# Schematic_Top_Rev4.net
KiCad netlist of a schematic drawn in Altium Designer
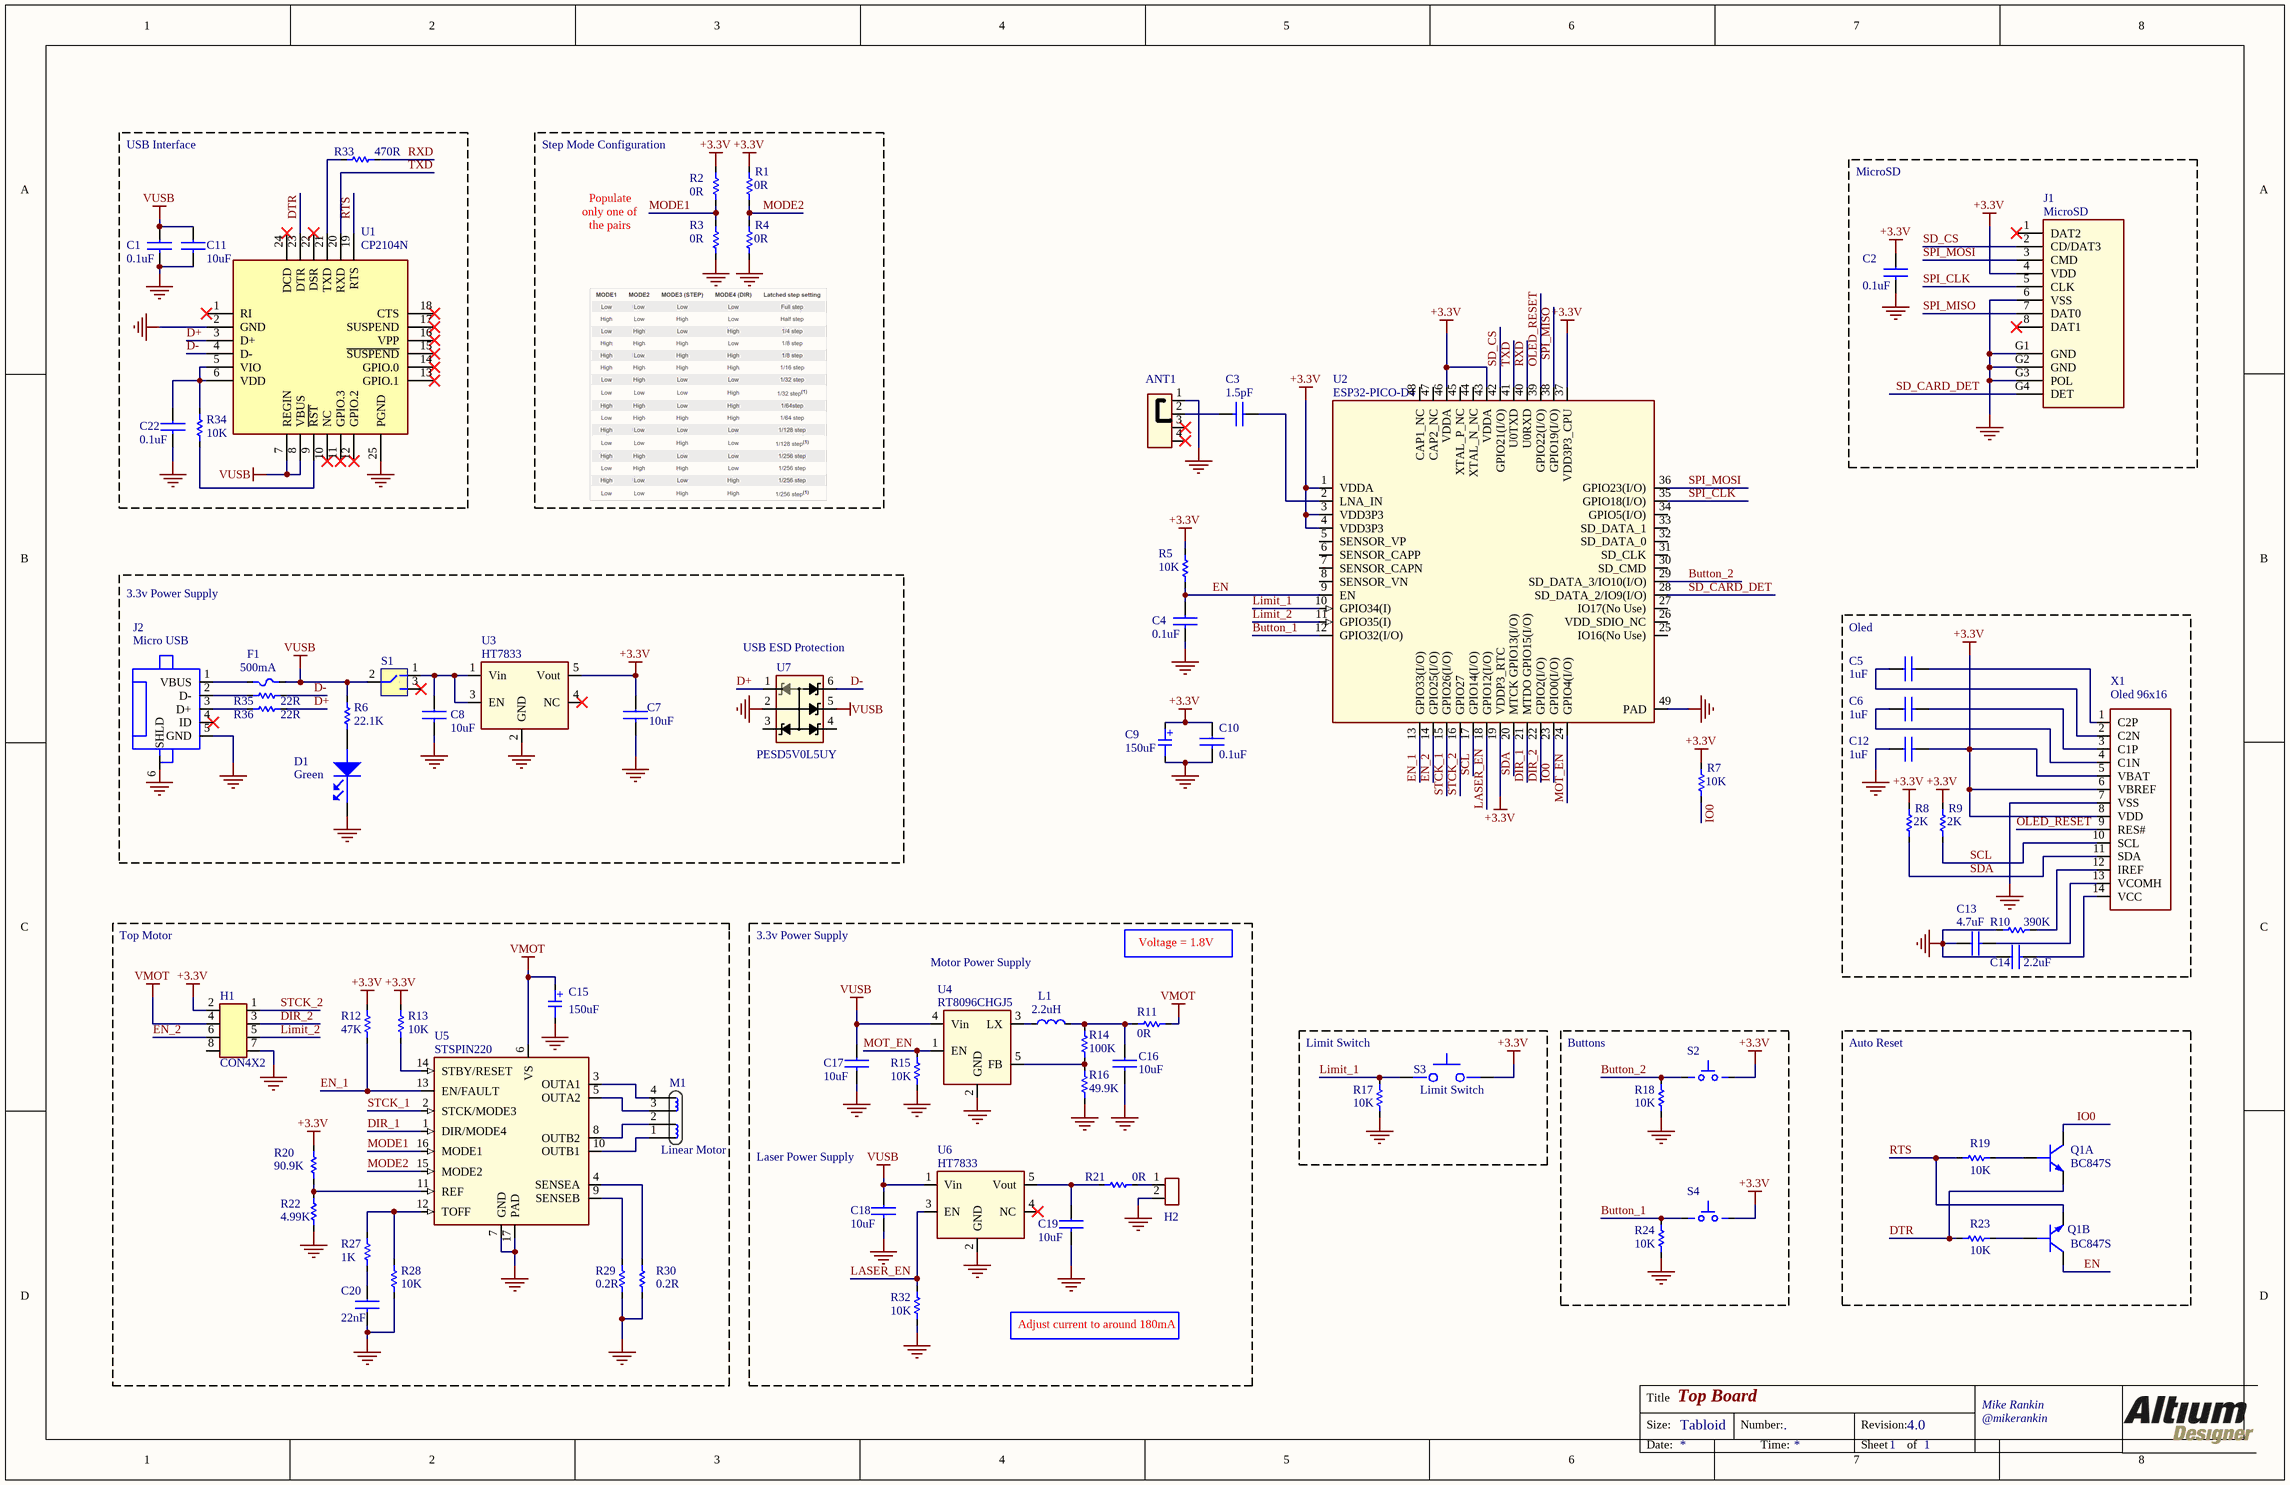
[diagram p0: Schematic_Top_Rev4.SchDoc]

(export (version "E")
  (design (tool "Eeschema 10.0.6"))
  (components
    (comp (ref "ANT1")
      (value "RF ANT 2.4GHZ STAMPED MET SLD")
      (footprint "PRO-OB-440")
      (fields (field (name "MANUFACTURER") "Proant AB") (field (name "PART_NUMBER") "PRO-OB-440"))
      (libsource (lib "MAR") (part "PRO-OB-440"))
    )
    (comp (ref "C1")
      (value "0.1uF")
      (footprint "CAPC1005X56N")
      (description "CAP 0.1uF 16V 0402")
      (fields (field (name "PART_NUMBER") "C60474") (field (name "MANUFACTURER") "Yageo"))
      (libsource (lib "MAR") (part "CAP_0402"))
    )
    (comp (ref "C2")
      (value "0.1uF")
      (footprint "CAPC1005X56N")
      (description "CAP 0.1uF 16V 0402")
      (fields (field (name "PART_NUMBER") "C60474") (field (name "MANUFACTURER") "Yageo"))
      (libsource (lib "MAR") (part "CAP_0402"))
    )
    (comp (ref "C3")
      (value "1.5pF")
      (footprint "CAPC1005X56N")
      (description "CAP 1.5pF 0402")
      (fields (field (name "PART_NUMBER") "C147344") (field (name "MANUFACTURER") "Dafron"))
      (libsource (lib "MAR") (part "CAP_0402"))
    )
    (comp (ref "C4")
      (value "0.1uF")
      (footprint "CAPC1005X56N")
      (description "CAP 0.1uF 16V 0402")
      (fields (field (name "PART_NUMBER") "C60474") (field (name "MANUFACTURER") "Yageo"))
      (libsource (lib "MAR") (part "CAP_0402"))
    )
    (comp (ref "C5")
      (value "1uF")
      (footprint "CAPC1005X56N")
      (description "CAP 0.1uF 16V 0402")
      (fields (field (name "PART_NUMBER") "C29266") (field (name "MANUFACTURER") "Samsung"))
      (libsource (lib "MAR") (part "CAP_0402"))
    )
    (comp (ref "C6")
      (value "1uF")
      (footprint "CAPC1005X56N")
      (description "CAP 0.1uF 16V 0402")
      (fields (field (name "PART_NUMBER") "C29266") (field (name "MANUFACTURER") "Samsung"))
      (libsource (lib "MAR") (part "CAP_0402"))
    )
    (comp (ref "C7")
      (value "10uF")
      (footprint "CAPC2012X140N")
      (description "CAP 10uF 16V 0805")
      (fields (field (name "MANUFACTURER") "Murata") (field (name "PART_NUMBER") "C162317"))
      (libsource (lib "MAR") (part "CAP_0805"))
    )
    (comp (ref "C8")
      (value "10uF")
      (footprint "CAPC2012X140N")
      (description "CAP 10uF 16V 0805")
      (fields (field (name "MANUFACTURER") "Murata") (field (name "PART_NUMBER") "C162317"))
      (libsource (lib "MAR") (part "CAP_0805"))
    )
    (comp (ref "C9")
      (value "150uF")
      (footprint "CAP_SM_CAN_0.250_DIA")
      (description "CAP 150uF, 10V SMT")
      (fields (field (name "PART_NUMBER") "C242018") (field (name "MANUFACTURER") "Suncon"))
      (libsource (lib "MAR") (part "CAP_ELEC_SMT"))
    )
    (comp (ref "C10")
      (value "0.1uF")
      (footprint "CAPC1005X56N")
      (description "CAP 0.1uF 16V 0402")
      (fields (field (name "PART_NUMBER") "C60474") (field (name "MANUFACTURER") "Yageo"))
      (libsource (lib "MAR") (part "CAP_0402"))
    )
    (comp (ref "C11")
      (value "10uF")
      (footprint "CAPC2012X140N")
      (description "CAP 10uF 16V 0805")
      (fields (field (name "MANUFACTURER") "Murata") (field (name "PART_NUMBER") "C162317"))
      (libsource (lib "MAR") (part "CAP_0805"))
    )
    (comp (ref "C12")
      (value "1uF")
      (footprint "CAPC1005X56N")
      (description "CAP 0.1uF 16V 0402")
      (fields (field (name "PART_NUMBER") "C29266") (field (name "MANUFACTURER") "Samsung"))
      (libsource (lib "MAR") (part "CAP_0402"))
    )
    (comp (ref "C13")
      (value "4.7uF")
      (footprint "CAPC1005X56N")
      (description "CAP 4.7uF 16V 0402")
      (fields (field (name "PART_NUMBER") "C318563") (field (name "MANUFACTURER") "Samsung"))
      (libsource (lib "MAR") (part "CAP_0402"))
    )
    (comp (ref "C14")
      (value "2.2uF")
      (footprint "CAPC1005X56N")
      (description "CAP 2.2uF 16V 0402")
      (fields (field (name "PART_NUMBER") "C170151") (field (name "MANUFACTURER") "Samsung"))
      (libsource (lib "MAR") (part "CAP_0402"))
    )
    (comp (ref "C15")
      (value "150uF")
      (footprint "CAP_SM_CAN_0.250_DIA")
      (description "CAP 150uF, 10V SMT")
      (fields (field (name "PART_NUMBER") "C242018") (field (name "MANUFACTURER") "Suncon"))
      (libsource (lib "MAR") (part "CAP_ELEC_SMT"))
    )
    (comp (ref "C16")
      (value "10uF")
      (footprint "CAPC2012X140N")
      (description "CAP 10uF 16V 0805")
      (fields (field (name "MANUFACTURER") "Murata") (field (name "PART_NUMBER") "C162317"))
      (libsource (lib "MAR") (part "CAP_0805"))
    )
    (comp (ref "C17")
      (value "10uF")
      (footprint "CAPC2012X140N")
      (description "CAP 10uF 16V 0805")
      (fields (field (name "MANUFACTURER") "Murata") (field (name "PART_NUMBER") "C162317"))
      (libsource (lib "MAR") (part "CAP_0805"))
    )
    (comp (ref "C18")
      (value "10uF")
      (footprint "CAPC2012X140N")
      (description "CAP 10uF 16V 0805")
      (fields (field (name "MANUFACTURER") "Murata") (field (name "PART_NUMBER") "C162317"))
      (libsource (lib "MAR") (part "CAP_0805"))
    )
    (comp (ref "C19")
      (value "10uF")
      (footprint "CAPC2012X140N")
      (description "CAP 10uF 16V 0805")
      (fields (field (name "MANUFACTURER") "Murata") (field (name "PART_NUMBER") "C162317"))
      (libsource (lib "MAR") (part "CAP_0805"))
    )
    (comp (ref "C20")
      (value "22nF")
      (footprint "CAPC1005X56N")
      (description "CAP 22nF 16V 0402")
      (fields (field (name "PART_NUMBER") "C318579") (field (name "MANUFACTURER") "Samsung"))
      (libsource (lib "MAR") (part "CAP_0402"))
    )
    (comp (ref "C22")
      (value "0.1uF")
      (footprint "CAPC1005X56N")
      (description "CAP 0.1uF 16V 0402")
      (fields (field (name "PART_NUMBER") "C60474") (field (name "MANUFACTURER") "Yageo"))
      (libsource (lib "MAR") (part "CAP_0402"))
    )
    (comp (ref "D1")
      (value "Green")
      (footprint "LED1608X55N-GREEN")
      (description "LED Green 0603")
      (fields (field (name "MANUFACTURER") "Orient") (field (name "PART_NUMBER") "C205443"))
      (libsource (lib "MAR") (part "LED_0603"))
    )
    (comp (ref "F1")
      (value "500mA")
      (footprint "PTC2012X70L")
      (description "6V 1A 100ms 0805 PTC Resettable Fuse")
      (fields (field (name "MANUFACTURER") "TLC") (field (name "PART_NUMBER") "C261942"))
      (libsource (lib "MAR") (part "PTC_FUSE"))
    )
    (comp (ref "H1")
      (value "CON4X2")
      (footprint "HDR2X4_RA")
      (description "CONN HEADER 4X2 POS .100\" RA")
      (fields (field (name "PART_NUMBER") "C358706") (field (name "MANUFACTURER") "MINTRON"))
      (libsource (lib "MAR") (part "CON4X2_M"))
    )
    (comp (ref "H2")
      (value "CON2")
      (footprint "HDR1X2-EMPTY")
      (description "EMPTY SOLDER 2POS")
      (libsource (lib "MAR") (part "CON2-EMPTY_PAD"))
    )
    (comp (ref "J1")
      (value "MicroSD")
      (footprint "0473092851")
      (description "9 (8 + 1) microSD SMT, Right Angle")
      (fields (field (name "MANUFACTURER") "Molex") (field (name "PART_NUMBER") "0473092851"))
      (libsource (lib "MAR") (part "0473092851"))
    )
    (comp (ref "J2")
      (value "Micro USB")
      (footprint "U254-051N-4BH806")
      (description "CONN RECPT MICRO USB")
      (fields (field (name "MANUFACTURER") "XKB") (field (name "PART_NUMBER") "C319170"))
      (libsource (lib "MAR") (part "U254-051N-4BH806"))
    )
    (comp (ref "L1")
      (value "2.2uH")
      (footprint "IND_2mmx2mm")
      (description "Inductor 2.2uH 1.45A 2.0 x 2.0mm")
      (fields (field (name "PART_NUMBER") "C90329") (field (name "MANUFACTURER") "Taiyo Yuden"))
      (libsource (lib "MAR") (part "Inductor"))
    )
    (comp (ref "M1")
      (value "Linear Motor")
      (footprint "Motor_Mini_Linear_1")
      (description "MTR,LINEAR,SMT")
      (fields (field (name "PART_NUMBER") "shorturl.at/cQ269"))
      (libsource (lib "MAR") (part "Motor_Mini_Linear"))
    )
    (comp (ref "Q1")
      (value "BC847S")
      (footprint "SOT65P210X110-6N")
      (description "TRANS 2NPN 44V 0.1A SC-70-6")
      (fields (field (name "MANUFACTURER") "Changjiang") (field (name "PART_NUMBER") "C148112"))
      (libsource (lib "MAR") (part "BC847S"))
    )
    (comp (ref "R1")
      (value "0R")
      (footprint "RESC1005X40L")
      (description "RES 0R 0402")
      (fields (field (name "MANUFACTURER") "Uniroyal"))
      (libsource (lib "MAR") (part "RES_0402"))
    )
    (comp (ref "R2")
      (value "0R")
      (footprint "RESC1005X40L")
      (description "RES 0R 0402")
      (fields (field (name "MANUFACTURER") "Uniroyal"))
      (libsource (lib "MAR") (part "RES_0402"))
    )
    (comp (ref "R3")
      (value "0R")
      (footprint "RESC1005X40L")
      (description "RES 0R 0402")
      (fields (field (name "MANUFACTURER") "Uniroyal"))
      (libsource (lib "MAR") (part "RES_0402"))
    )
    (comp (ref "R4")
      (value "0R")
      (footprint "RESC1005X40L")
      (description "RES 0R 0402")
      (fields (field (name "MANUFACTURER") "Uniroyal"))
      (libsource (lib "MAR") (part "RES_0402"))
    )
    (comp (ref "R5")
      (value "10K")
      (footprint "RESC1005X40L")
      (description "RES 10K 0402")
      (fields (field (name "PART_NUMBER") "C25744") (field (name "MANUFACTURER") "Uniroyal"))
      (libsource (lib "MAR") (part "RES_0402"))
    )
    (comp (ref "R6")
      (value "22.1K")
      (footprint "RESC1005X40L")
      (description "RES 22.1K 0402")
      (fields (field (name "MANUFACTURER") "Uniroyal") (field (name "PART_NUMBER") "C43473"))
      (libsource (lib "MAR") (part "RES_0603"))
    )
    (comp (ref "R7")
      (value "10K")
      (footprint "RESC1005X40L")
      (description "RES 10K 0402")
      (fields (field (name "PART_NUMBER") "C25744") (field (name "MANUFACTURER") "Uniroyal"))
      (libsource (lib "MAR") (part "RES_0402"))
    )
    (comp (ref "R8")
      (value "2K")
      (footprint "RESC1005X40L")
      (description "RES 2K 0402")
      (fields (field (name "PART_NUMBER") "C4109") (field (name "MANUFACTURER") "Uniroyal"))
      (libsource (lib "MAR") (part "RES_0402"))
    )
    (comp (ref "R9")
      (value "2K")
      (footprint "RESC1005X40L")
      (description "RES 2K 0402")
      (fields (field (name "PART_NUMBER") "C4109") (field (name "MANUFACTURER") "Uniroyal"))
      (libsource (lib "MAR") (part "RES_0402"))
    )
    (comp (ref "R10")
      (value "390K")
      (footprint "RESC1005X40L")
      (description "RES 390K 0402")
      (fields (field (name "PART_NUMBER") "C25782") (field (name "MANUFACTURER") "Uniroyal"))
      (libsource (lib "MAR") (part "RES_0402"))
    )
    (comp (ref "R11")
      (value "0R")
      (footprint "RESC1005X40L")
      (description "RES 0R 0402")
      (fields (field (name "PART_NUMBER") "C17168") (field (name "MANUFACTURER") "Uniroyal"))
      (libsource (lib "MAR") (part "RES_0402"))
    )
    (comp (ref "R12")
      (value "47K")
      (footprint "RESC1005X40L")
      (description "RES 47K 0402")
      (fields (field (name "PART_NUMBER") "C25792") (field (name "MANUFACTURER") "Uniroyal"))
      (libsource (lib "MAR") (part "RES_0402"))
    )
    (comp (ref "R13")
      (value "10K")
      (footprint "RESC1005X40L")
      (description "RES 10K 0402")
      (fields (field (name "PART_NUMBER") "C25744") (field (name "MANUFACTURER") "Uniroyal"))
      (libsource (lib "MAR") (part "RES_0402"))
    )
    (comp (ref "R14")
      (value "100K")
      (footprint "RESC1005X40L")
      (description "RES 100K 0402")
      (fields (field (name "PART_NUMBER") "C25741") (field (name "MANUFACTURER") "Uniroyal"))
      (libsource (lib "MAR") (part "RES_0402"))
    )
    (comp (ref "R15")
      (value "10K")
      (footprint "RESC1005X40L")
      (description "RES 10K 0402")
      (fields (field (name "PART_NUMBER") "C25744") (field (name "MANUFACTURER") "Uniroyal"))
      (libsource (lib "MAR") (part "RES_0402"))
    )
    (comp (ref "R16")
      (value "49.9K")
      (footprint "RESC1005X40L")
      (description "RES 49.9K 0402")
      (fields (field (name "PART_NUMBER") "C25897") (field (name "MANUFACTURER") "Uniroyal"))
      (libsource (lib "MAR") (part "RES_0402"))
    )
    (comp (ref "R17")
      (value "10K")
      (footprint "RESC1005X40L")
      (description "RES 10K 0402")
      (fields (field (name "PART_NUMBER") "C25744") (field (name "MANUFACTURER") "Uniroyal"))
      (libsource (lib "MAR") (part "RES_0402"))
    )
    (comp (ref "R18")
      (value "10K")
      (footprint "RESC1005X40L")
      (description "RES 10K 0402")
      (fields (field (name "PART_NUMBER") "C25744") (field (name "MANUFACTURER") "Uniroyal"))
      (libsource (lib "MAR") (part "RES_0402"))
    )
    (comp (ref "R19")
      (value "10K")
      (footprint "RESC1005X40L")
      (description "RES 10K 0402")
      (fields (field (name "PART_NUMBER") "C25744") (field (name "MANUFACTURER") "Uniroyal"))
      (libsource (lib "MAR") (part "RES_0402"))
    )
    (comp (ref "R20")
      (value "90.9K")
      (footprint "RESC1005X40L")
      (description "RES 90.9K 0402")
      (fields (field (name "PART_NUMBER") "C26989") (field (name "MANUFACTURER") "Uniroyal"))
      (libsource (lib "MAR") (part "RES_0402"))
    )
    (comp (ref "R21")
      (value "0R")
      (footprint "RESC1005X40L")
      (description "RES 0R 0402")
      (fields (field (name "PART_NUMBER") "C17168") (field (name "MANUFACTURER") "Uniroyal"))
      (libsource (lib "MAR") (part "RES_0402"))
    )
    (comp (ref "R22")
      (value "4.99K")
      (footprint "RESC1005X40L")
      (description "RES 4.99K 0402")
      (fields (field (name "PART_NUMBER") "C25903") (field (name "MANUFACTURER") "Uniroyal"))
      (libsource (lib "MAR") (part "RES_0402"))
    )
    (comp (ref "R23")
      (value "10K")
      (footprint "RESC1005X40L")
      (description "RES 10K 0402")
      (fields (field (name "PART_NUMBER") "C25744") (field (name "MANUFACTURER") "Uniroyal"))
      (libsource (lib "MAR") (part "RES_0402"))
    )
    (comp (ref "R24")
      (value "10K")
      (footprint "RESC1005X40L")
      (description "RES 10K 0402")
      (fields (field (name "PART_NUMBER") "C25744") (field (name "MANUFACTURER") "Uniroyal"))
      (libsource (lib "MAR") (part "RES_0402"))
    )
    (comp (ref "R27")
      (value "1K")
      (footprint "RESC1005X40L")
      (description "RES 1K 0402")
      (fields (field (name "PART_NUMBER") "C11702") (field (name "MANUFACTURER") "Uniroyal"))
      (libsource (lib "MAR") (part "RES_0402"))
    )
    (comp (ref "R28")
      (value "10K")
      (footprint "RESC1005X40L")
      (description "RES 10K 0402")
      (fields (field (name "PART_NUMBER") "C25744") (field (name "MANUFACTURER") "Uniroyal"))
      (libsource (lib "MAR") (part "RES_0402"))
    )
    (comp (ref "R29")
      (value "0.2R")
      (footprint "RESC1005X40L")
      (description "RES 0.2R 0402")
      (fields (field (name "PART_NUMBER") "C270629") (field (name "MANUFACTURER") "Uniroyal"))
      (libsource (lib "MAR") (part "RES_0402"))
    )
    (comp (ref "R30")
      (value "0.2R")
      (footprint "RESC1005X40L")
      (description "RES 0.2R 0402")
      (fields (field (name "PART_NUMBER") "C270629") (field (name "MANUFACTURER") "Uniroyal"))
      (libsource (lib "MAR") (part "RES_0402"))
    )
    (comp (ref "R32")
      (value "10K")
      (footprint "RESC1005X40L")
      (description "RES 10K 0402")
      (fields (field (name "PART_NUMBER") "C25744") (field (name "MANUFACTURER") "Uniroyal"))
      (libsource (lib "MAR") (part "RES_0402"))
    )
    (comp (ref "R33")
      (value "470R")
      (footprint "RESC1005X40L")
      (description "RES 470R 0402")
      (fields (field (name "PART_NUMBER") "C25117") (field (name "MANUFACTURER") "Uniroyal"))
      (libsource (lib "MAR") (part "RES_0402"))
    )
    (comp (ref "R34")
      (value "10K")
      (footprint "RESC1005X40L")
      (description "RES 10K 0402")
      (fields (field (name "PART_NUMBER") "C25744") (field (name "MANUFACTURER") "Uniroyal"))
      (libsource (lib "MAR") (part "RES_0402"))
    )
    (comp (ref "R35")
      (value "22R")
      (footprint "RESC1005X40L")
      (description "RES 22R 0402")
      (fields (field (name "PART_NUMBER") "C25092") (field (name "MANUFACTURER") "Uniroyal"))
      (libsource (lib "MAR") (part "RES_0402"))
    )
    (comp (ref "R36")
      (value "22R")
      (footprint "RESC1005X40L")
      (description "RES 22R 0402")
      (fields (field (name "PART_NUMBER") "C25092") (field (name "MANUFACTURER") "Uniroyal"))
      (libsource (lib "MAR") (part "RES_0402"))
    )
    (comp (ref "S1")
      (value "Toggle Switch")
      (footprint "SK-3245D-02-L4")
      (description "Toggle Switch Thu Hole")
      (fields (field (name "MANUFACTURER") "XKB") (field (name "PART_NUMBER") "C381099"))
      (libsource (lib "MAR") (part "SK-3245D-02-L4"))
    )
    (comp (ref "S2")
      (value "Pushbutton")
      (footprint "TL1015AF160QG")
      (description "Switch SMD,3x4x2.5mm")
      (fields (field (name "PART_NUMBER") "C455281") (field (name "MANUFACTURER") "Xunpu"))
      (libsource (lib "MAR") (part "TL1015AF160QG"))
    )
    (comp (ref "S3")
      (value "Limit Switch")
      (footprint "SSCQ110100")
      (description "SWITCH DETECT, DUAL, SMD,R/A")
      (fields (field (name "PART_NUMBER") "C231760") (field (name "MANUFACTURER") "Alps"))
      (libsource (lib "MAR") (part "SSCQ110100"))
    )
    (comp (ref "S4")
      (value "Pushbutton")
      (footprint "TL1015AF160QG")
      (description "Switch SMD,3x4x2.5mm")
      (fields (field (name "PART_NUMBER") "C455281") (field (name "MANUFACTURER") "Xunpu"))
      (libsource (lib "MAR") (part "TL1015AF160QG"))
    )
    (comp (ref "U1")
      (value "CP2104N")
      (footprint "24-QFN")
      (description "IC BRIDGE USB TO UART 24QFN")
      (fields (field (name "MANUFACTURER") "Silicon Labs") (field (name "PART_NUMBER") "CP2104-F03-GMR"))
      (libsource (lib "MAR") (part "CP2104N"))
    )
    (comp (ref "U2")
      (value "ESP32-PICO-D4")
      (footprint "QFN48")
      (description "WIFI/Bluetooth, QFN-48 7x7")
      (fields (field (name "MANUFACTURER") "Espressif"))
      (libsource (lib "MAR") (part "ESP32-PICO-D4"))
    )
    (comp (ref "U3")
      (value "HT7833")
      (footprint "SOT95P280X144-5N")
      (description "IC LDO 3.3V 0.5A SOT23-5")
      (fields (field (name "MANUFACTURER") "Holtek") (field (name "PART_NUMBER") "C164106"))
      (libsource (lib "MAR") (part "HT7833"))
    )
    (comp (ref "U4")
      (value "RT8096CHGJ5")
      (footprint "SOT95P280X144-5N")
      (description "IC DC SWITCHING REG 1A SOT23-5")
      (fields (field (name "MANUFACTURER") "Richtek") (field (name "PART_NUMBER") "RT8096CHGJ5"))
      (libsource (lib "MAR") (part "RT8096CHGJ5"))
    )
    (comp (ref "U5")
      (value "STSPIN220")
      (footprint "16QFN")
      (description "IC STEPPER MOTOR DRIVER 16-VFQFPN(3x3)")
      (fields (field (name "MANUFACTURER") "ST Micro") (field (name "PART_NUMBER") "STSPIN220"))
      (libsource (lib "MAR") (part "STSPIN220"))
    )
    (comp (ref "U6")
      (value "HT7833")
      (footprint "SOT95P280X144-5N")
      (description "IC LDO 3.3V 0.5A SOT23-5")
      (fields (field (name "MANUFACTURER") "Holtek") (field (name "PART_NUMBER") "C164106"))
      (libsource (lib "MAR") (part "HT7833"))
    )
    (comp (ref "U7")
      (value "PESD5V0L5UY")
      (footprint "SOT65P210X110-6N")
      (description "TVS 5V SOT-363")
      (fields (field (name "MANUFACTURER") "Yenji") (field (name "PART_NUMBER") "PESD5V0L5UY"))
      (libsource (lib "MAR") (part "PESD5V0L5UY"))
    )
    (comp (ref "X1")
      (value "OLED_GLASS 96x16")
      (footprint "OLED_GLASS 96x16")
      (description "96x16 OLED_GLASS")
      (fields (field (name "PART_NUMBER") "ER-OLED0.69-1W"))
      (libsource (lib "MAR") (part "OLED_GLASS 96x16"))
    )
  )
  (nets
    (net (code "1") (name "+3.3V") (class "Default")
      (node (ref "C10") (pin "1") (pinfunction "1_1") (pintype "passive"))
      (node (ref "C12") (pin "2") (pinfunction "2_2") (pintype "passive"))
      (node (ref "C2") (pin "1") (pinfunction "1_1") (pintype "passive"))
      (node (ref "C7") (pin "1") (pinfunction "1_1") (pintype "passive"))
      (node (ref "C9") (pin "1") (pintype "passive"))
      (node (ref "H1") (pin "2") (pintype "passive"))
      (node (ref "J1") (pin "4") (pinfunction "VDD_4") (pintype "power_in"))
      (node (ref "R1") (pin "1") (pintype "passive"))
      (node (ref "R12") (pin "2") (pintype "passive"))
      (node (ref "R13") (pin "2") (pintype "passive"))
      (node (ref "R2") (pin "2") (pintype "passive"))
      (node (ref "R20") (pin "2") (pintype "passive"))
      (node (ref "R5") (pin "1") (pintype "passive"))
      (node (ref "R7") (pin "1") (pintype "passive"))
      (node (ref "R8") (pin "1") (pintype "passive"))
      (node (ref "R9") (pin "1") (pintype "passive"))
      (node (ref "S2") (pin "2") (pinfunction "B_2") (pintype "passive"))
      (node (ref "S3") (pin "2") (pinfunction "B_2") (pintype "passive"))
      (node (ref "S4") (pin "2") (pinfunction "B_2") (pintype "passive"))
      (node (ref "U2") (pin "1") (pinfunction "VDDA_1") (pintype "power_in"))
      (node (ref "U2") (pin "19") (pinfunction "VDDP3_RTC_19") (pintype "passive"))
      (node (ref "U2") (pin "3") (pinfunction "VDD3P3_3") (pintype "power_in"))
      (node (ref "U2") (pin "37") (pinfunction "VDD3P3_CPU_37") (pintype "power_in"))
      (node (ref "U2") (pin "4") (pinfunction "VDD3P3_4") (pintype "power_in"))
      (node (ref "U2") (pin "43") (pinfunction "VDDA_43") (pintype "power_in"))
      (node (ref "U2") (pin "46") (pinfunction "VDDA_46") (pintype "power_in"))
      (node (ref "U3") (pin "5") (pinfunction "Vout_5") (pintype "passive"))
      (node (ref "X1") (pin "5") (pinfunction "VBAT_5") (pintype "passive"))
      (node (ref "X1") (pin "6") (pinfunction "VBREF_6") (pintype "passive"))
      (node (ref "X1") (pin "8") (pinfunction "VDD_8") (pintype "passive"))
    )
    (net (code "2") (name "/Button_1") (class "Default")
      (node (ref "R24") (pin "1") (pintype "passive"))
      (node (ref "S4") (pin "1") (pinfunction "A_1") (pintype "passive"))
      (node (ref "U2") (pin "12") (pinfunction "GPIO32(I/O)_12") (pintype "passive"))
    )
    (net (code "3") (name "/Button_2") (class "Default")
      (node (ref "R18") (pin "1") (pintype "passive"))
      (node (ref "S2") (pin "1") (pinfunction "A_1") (pintype "passive"))
      (node (ref "U2") (pin "29") (pinfunction "SD_DATA_3/IO10(I/O)_29") (pintype "passive"))
    )
    (net (code "4") (name "/D+") (class "Default")
      (node (ref "R36") (pin "1") (pintype "passive"))
      (node (ref "U1") (pin "3") (pinfunction "D+_3") (pintype "passive"))
      (node (ref "U7") (pin "1") (pinfunction "1_1") (pintype "passive"))
    )
    (net (code "5") (name "/D-") (class "Default")
      (node (ref "R35") (pin "1") (pintype "passive"))
      (node (ref "U1") (pin "4") (pinfunction "D-_4") (pintype "passive"))
      (node (ref "U7") (pin "6") (pinfunction "6_6") (pintype "passive"))
    )
    (net (code "6") (name "/DIR_1") (class "Default")
      (node (ref "U2") (pin "21") (pinfunction "MTDO_GPIO15(I/O)_21") (pintype "passive"))
      (node (ref "U5") (pin "1") (pinfunction "DIR/MODE4_1") (pintype "input"))
    )
    (net (code "7") (name "/DIR_2") (class "Default")
      (node (ref "H1") (pin "3") (pintype "passive"))
      (node (ref "U2") (pin "22") (pinfunction "GPIO2(I/O)_22") (pintype "passive"))
    )
    (net (code "8") (name "/DTR") (class "Default")
      (node (ref "Q1") (pin "1") (pinfunction "E1_1") (pintype "passive"))
      (node (ref "R23") (pin "2") (pintype "passive"))
      (node (ref "U1") (pin "23") (pinfunction "DTR_23") (pintype "passive"))
    )
    (net (code "9") (name "/EN") (class "Default")
      (node (ref "C4") (pin "1") (pinfunction "1_1") (pintype "passive"))
      (node (ref "Q1") (pin "3") (pinfunction "C2_3") (pintype "passive"))
      (node (ref "R5") (pin "2") (pintype "passive"))
      (node (ref "U2") (pin "9") (pinfunction "EN_9") (pintype "passive"))
    )
    (net (code "10") (name "/EN_1") (class "Default")
      (node (ref "R12") (pin "1") (pintype "passive"))
      (node (ref "U2") (pin "13") (pinfunction "GPIO33(I/O)_13") (pintype "passive"))
      (node (ref "U5") (pin "13") (pinfunction "EN/FAULT_13") (pintype "passive"))
    )
    (net (code "11") (name "/EN_2") (class "Default")
      (node (ref "H1") (pin "6") (pintype "passive"))
      (node (ref "U2") (pin "14") (pinfunction "GPIO25(I/O)_14") (pintype "passive"))
    )
    (net (code "12") (name "/IO0") (class "Default")
      (node (ref "Q1") (pin "6") (pinfunction "C1_6") (pintype "passive"))
      (node (ref "R7") (pin "2") (pintype "passive"))
      (node (ref "U2") (pin "23") (pinfunction "GPIO0(I/O)_23") (pintype "passive"))
    )
    (net (code "13") (name "/LASER_EN") (class "Default")
      (node (ref "R32") (pin "2") (pintype "passive"))
      (node (ref "U2") (pin "18") (pinfunction "GPIO12(I/O)_18") (pintype "passive"))
      (node (ref "U6") (pin "3") (pinfunction "EN_3") (pintype "passive"))
    )
    (net (code "14") (name "/Limit_1") (class "Default")
      (node (ref "R17") (pin "1") (pintype "passive"))
      (node (ref "S3") (pin "1") (pinfunction "A_1") (pintype "passive"))
      (node (ref "U2") (pin "10") (pinfunction "GPIO34(I)_10") (pintype "input"))
    )
    (net (code "15") (name "/Limit_2") (class "Default")
      (node (ref "H1") (pin "5") (pintype "passive"))
      (node (ref "U2") (pin "11") (pinfunction "GPIO35(I)_11") (pintype "input"))
    )
    (net (code "16") (name "/MODE1") (class "Default")
      (node (ref "R2") (pin "1") (pintype "passive"))
      (node (ref "R3") (pin "1") (pintype "passive"))
      (node (ref "U5") (pin "16") (pinfunction "MODE1_16") (pintype "input"))
    )
    (net (code "17") (name "/MODE2") (class "Default")
      (node (ref "R1") (pin "2") (pintype "passive"))
      (node (ref "R4") (pin "1") (pintype "passive"))
      (node (ref "U5") (pin "15") (pinfunction "MODE2_15") (pintype "input"))
    )
    (net (code "18") (name "/MOT_EN") (class "Default")
      (node (ref "R15") (pin "2") (pintype "passive"))
      (node (ref "U2") (pin "24") (pinfunction "GPIO4(I/O)_24") (pintype "passive"))
      (node (ref "U4") (pin "1") (pinfunction "EN_1") (pintype "passive"))
    )
    (net (code "19") (name "/OLED_RESET") (class "Default")
      (node (ref "U2") (pin "39") (pinfunction "GPIO22(I/O)_39") (pintype "passive"))
      (node (ref "X1") (pin "9") (pinfunction "RES#_9") (pintype "passive"))
    )
    (net (code "20") (name "/RTS") (class "Default")
      (node (ref "Q1") (pin "4") (pinfunction "E2_4") (pintype "passive"))
      (node (ref "R19") (pin "2") (pintype "passive"))
      (node (ref "U1") (pin "19") (pinfunction "RTS_19") (pintype "passive"))
    )
    (net (code "21") (name "/RXD") (class "Default")
      (node (ref "R33") (pin "1") (pintype "passive"))
      (node (ref "U2") (pin "40") (pinfunction "U0RXD_40") (pintype "passive"))
    )
    (net (code "22") (name "/SCL") (class "Default")
      (node (ref "R9") (pin "2") (pintype "passive"))
      (node (ref "U2") (pin "17") (pinfunction "GPIO14(I/O)_17") (pintype "passive"))
      (node (ref "X1") (pin "10") (pinfunction "SCL_10") (pintype "passive"))
    )
    (net (code "23") (name "/SDA") (class "Default")
      (node (ref "R8") (pin "2") (pintype "passive"))
      (node (ref "U2") (pin "20") (pinfunction "MTCK_GPIO13(I/O)_20") (pintype "passive"))
      (node (ref "X1") (pin "11") (pinfunction "SDA_11") (pintype "passive"))
    )
    (net (code "24") (name "/SD_CARD_DET") (class "Default")
      (node (ref "J1") (pin "G4") (pinfunction "DET_G4") (pintype "power_in"))
      (node (ref "U2") (pin "28") (pinfunction "SD_DATA_2/IO9(I/O)_28") (pintype "passive"))
    )
    (net (code "25") (name "/SD_CS") (class "Default")
      (node (ref "J1") (pin "2") (pinfunction "CD/DAT3_2") (pintype "power_in"))
      (node (ref "U2") (pin "42") (pinfunction "GPIO21(I/O)_42") (pintype "passive"))
    )
    (net (code "26") (name "/SPI_CLK") (class "Default")
      (node (ref "J1") (pin "5") (pinfunction "CLK_5") (pintype "power_in"))
      (node (ref "U2") (pin "35") (pinfunction "GPIO18(I/O)_35") (pintype "passive"))
    )
    (net (code "27") (name "/SPI_MISO") (class "Default")
      (node (ref "J1") (pin "7") (pinfunction "DAT0_7") (pintype "power_in"))
      (node (ref "U2") (pin "38") (pinfunction "GPIO19(I/O)_38") (pintype "passive"))
    )
    (net (code "28") (name "/SPI_MOSI") (class "Default")
      (node (ref "J1") (pin "3") (pinfunction "CMD_3") (pintype "power_in"))
      (node (ref "U2") (pin "36") (pinfunction "GPIO23(I/O)_36") (pintype "passive"))
    )
    (net (code "29") (name "/STCK_1") (class "Default")
      (node (ref "U2") (pin "15") (pinfunction "GPIO26(I/O)_15") (pintype "passive"))
      (node (ref "U5") (pin "2") (pinfunction "STCK/MODE3_2") (pintype "input"))
    )
    (net (code "30") (name "/STCK_2") (class "Default")
      (node (ref "H1") (pin "1") (pintype "passive"))
      (node (ref "U2") (pin "16") (pinfunction "GPIO27_16") (pintype "passive"))
    )
    (net (code "31") (name "/TXD") (class "Default")
      (node (ref "U1") (pin "20") (pinfunction "RXD_20") (pintype "passive"))
      (node (ref "U2") (pin "41") (pinfunction "U0TXD_41") (pintype "passive"))
    )
    (net (code "32") (name "GND") (class "Default")
      (node (ref "ANT1") (pin "1") (pintype "passive"))
      (node (ref "C1") (pin "2") (pinfunction "2_2") (pintype "passive"))
      (node (ref "C10") (pin "2") (pinfunction "2_2") (pintype "passive"))
      (node (ref "C11") (pin "2") (pinfunction "2_2") (pintype "passive"))
      (node (ref "C12") (pin "1") (pinfunction "1_1") (pintype "passive"))
      (node (ref "C13") (pin "1") (pinfunction "1_1") (pintype "passive"))
      (node (ref "C14") (pin "1") (pinfunction "1_1") (pintype "passive"))
      (node (ref "C15") (pin "2") (pintype "passive"))
      (node (ref "C16") (pin "2") (pinfunction "2_2") (pintype "passive"))
      (node (ref "C17") (pin "2") (pinfunction "2_2") (pintype "passive"))
      (node (ref "C18") (pin "2") (pinfunction "2_2") (pintype "passive"))
      (node (ref "C19") (pin "2") (pinfunction "2_2") (pintype "passive"))
      (node (ref "C2") (pin "2") (pinfunction "2_2") (pintype "passive"))
      (node (ref "C20") (pin "2") (pinfunction "2_2") (pintype "passive"))
      (node (ref "C22") (pin "2") (pinfunction "2_2") (pintype "passive"))
      (node (ref "C4") (pin "2") (pinfunction "2_2") (pintype "passive"))
      (node (ref "C7") (pin "2") (pinfunction "2_2") (pintype "passive"))
      (node (ref "C8") (pin "2") (pinfunction "2_2") (pintype "passive"))
      (node (ref "C9") (pin "2") (pintype "passive"))
      (node (ref "D1") (pin "1") (pinfunction "CATHODE_1") (pintype "passive"))
      (node (ref "H1") (pin "7") (pintype "passive"))
      (node (ref "H2") (pin "2") (pintype "passive"))
      (node (ref "J1") (pin "6") (pinfunction "VSS_6") (pintype "power_in"))
      (node (ref "J1") (pin "G1") (pinfunction "GND_G1") (pintype "power_in"))
      (node (ref "J1") (pin "G2") (pinfunction "GND_G2") (pintype "power_in"))
      (node (ref "J1") (pin "G3") (pinfunction "POL_G3") (pintype "power_in"))
      (node (ref "J2") (pin "5") (pinfunction "GND_5") (pintype "power_in"))
      (node (ref "J2") (pin "6") (pinfunction "SHLD_6") (pintype "power_in"))
      (node (ref "R10") (pin "1") (pintype "passive"))
      (node (ref "R15") (pin "1") (pintype "passive"))
      (node (ref "R16") (pin "1") (pintype "passive"))
      (node (ref "R17") (pin "2") (pintype "passive"))
      (node (ref "R18") (pin "2") (pintype "passive"))
      (node (ref "R22") (pin "1") (pintype "passive"))
      (node (ref "R24") (pin "2") (pintype "passive"))
      (node (ref "R28") (pin "1") (pintype "passive"))
      (node (ref "R29") (pin "1") (pintype "passive"))
      (node (ref "R3") (pin "2") (pintype "passive"))
      (node (ref "R30") (pin "1") (pintype "passive"))
      (node (ref "R32") (pin "1") (pintype "passive"))
      (node (ref "R4") (pin "2") (pintype "passive"))
      (node (ref "U1") (pin "2") (pinfunction "GND_2") (pintype "power_in"))
      (node (ref "U1") (pin "25") (pinfunction "PGND_25") (pintype "passive"))
      (node (ref "U2") (pin "49") (pinfunction "PAD_49") (pintype "power_in"))
      (node (ref "U3") (pin "2") (pinfunction "GND_2") (pintype "power_in"))
      (node (ref "U4") (pin "2") (pinfunction "GND_2") (pintype "power_in"))
      (node (ref "U5") (pin "17") (pinfunction "PAD_17") (pintype "power_in"))
      (node (ref "U5") (pin "7") (pinfunction "GND_7") (pintype "power_in"))
      (node (ref "U6") (pin "2") (pinfunction "GND_2") (pintype "power_in"))
      (node (ref "U7") (pin "2") (pinfunction "2_2") (pintype "passive"))
      (node (ref "X1") (pin "7") (pinfunction "VSS_7") (pintype "passive"))
    )
    (net (code "33") (name "Net-(ANT1-Pad2)") (class "Default")
      (node (ref "ANT1") (pin "2") (pintype "passive"))
      (node (ref "C3") (pin "2") (pinfunction "2_2") (pintype "passive"))
    )
    (net (code "34") (name "Net-(C16-Pad1)") (class "Default")
      (node (ref "C16") (pin "1") (pinfunction "1_1") (pintype "passive"))
      (node (ref "L1") (pin "2") (pinfunction "2_2") (pintype "passive"))
      (node (ref "R11") (pin "2") (pintype "passive"))
      (node (ref "R14") (pin "2") (pintype "passive"))
    )
    (net (code "35") (name "Net-(C20-Pad1)") (class "Default")
      (node (ref "C20") (pin "1") (pinfunction "1_1") (pintype "passive"))
      (node (ref "R27") (pin "1") (pintype "passive"))
    )
    (net (code "36") (name "Net-(D1-ANODE)") (class "Default")
      (node (ref "D1") (pin "2") (pinfunction "ANODE_2") (pintype "passive"))
      (node (ref "R6") (pin "1") (pintype "passive"))
    )
    (net (code "37") (name "Net-(H2-Pad1)") (class "Default")
      (node (ref "H2") (pin "1") (pintype "passive"))
      (node (ref "R21") (pin "2") (pintype "passive"))
    )
    (net (code "38") (name "Net-(J2-D+)") (class "Default")
      (node (ref "J2") (pin "3") (pinfunction "D+_3") (pintype "passive"))
      (node (ref "R36") (pin "2") (pintype "passive"))
    )
    (net (code "39") (name "Net-(J2-D-)") (class "Default")
      (node (ref "J2") (pin "2") (pinfunction "D-_2") (pintype "passive"))
      (node (ref "R35") (pin "2") (pintype "passive"))
    )
    (net (code "40") (name "Net-(J2-VBUS)") (class "Default")
      (node (ref "F1") (pin "2") (pintype "passive"))
      (node (ref "J2") (pin "1") (pinfunction "VBUS_1") (pintype "power_in"))
    )
    (net (code "41") (name "Net-(Q1A-B1)") (class "Default")
      (node (ref "Q1") (pin "2") (pinfunction "B1_2") (pintype "passive"))
      (node (ref "R19") (pin "1") (pintype "passive"))
    )
    (net (code "42") (name "Net-(Q1B-B2)") (class "Default")
      (node (ref "Q1") (pin "5") (pinfunction "B2_5") (pintype "passive"))
      (node (ref "R23") (pin "1") (pintype "passive"))
    )
    (net (code "43") (name "Net-(U1-TXD)") (class "Default")
      (node (ref "R33") (pin "2") (pintype "passive"))
      (node (ref "U1") (pin "21") (pinfunction "TXD_21") (pintype "passive"))
    )
    (net (code "44") (name "Net-(U1-VDD)") (class "Default")
      (node (ref "C22") (pin "1") (pinfunction "1_1") (pintype "passive"))
      (node (ref "R34") (pin "1") (pintype "passive"))
      (node (ref "U1") (pin "5") (pinfunction "VIO_5") (pintype "power_in"))
      (node (ref "U1") (pin "6") (pinfunction "VDD_6") (pintype "power_in"))
    )
    (net (code "45") (name "Net-(U1-~{RST})") (class "Default")
      (node (ref "R34") (pin "2") (pintype "passive"))
      (node (ref "U1") (pin "9") (pinfunction "~{RST}_9") (pintype "passive"))
    )
    (net (code "46") (name "Net-(U2-LNA_IN)") (class "Default")
      (node (ref "C3") (pin "1") (pinfunction "1_1") (pintype "passive"))
      (node (ref "U2") (pin "2") (pinfunction "LNA_IN_2") (pintype "passive"))
    )
    (net (code "47") (name "Net-(U3-EN)") (class "Default")
      (node (ref "C8") (pin "1") (pinfunction "1_1") (pintype "passive"))
      (node (ref "S1") (pin "1") (pinfunction "1_1") (pintype "passive"))
      (node (ref "U3") (pin "1") (pinfunction "Vin_1") (pintype "passive"))
      (node (ref "U3") (pin "3") (pinfunction "EN_3") (pintype "passive"))
    )
    (net (code "48") (name "Net-(U4-FB)") (class "Default")
      (node (ref "R14") (pin "1") (pintype "passive"))
      (node (ref "R16") (pin "2") (pintype "passive"))
      (node (ref "U4") (pin "5") (pinfunction "FB_5") (pintype "passive"))
    )
    (net (code "49") (name "Net-(U4-LX)") (class "Default")
      (node (ref "L1") (pin "1") (pinfunction "1_1") (pintype "passive"))
      (node (ref "U4") (pin "3") (pinfunction "LX_3") (pintype "passive"))
    )
    (net (code "50") (name "Net-(U5-OUTA1)") (class "Default")
      (node (ref "M1") (pin "4") (pintype "passive"))
      (node (ref "U5") (pin "3") (pinfunction "OUTA1_3") (pintype "passive"))
    )
    (net (code "51") (name "Net-(U5-OUTA2)") (class "Default")
      (node (ref "M1") (pin "3") (pintype "passive"))
      (node (ref "U5") (pin "5") (pinfunction "OUTA2_5") (pintype "passive"))
    )
    (net (code "52") (name "Net-(U5-OUTB1)") (class "Default")
      (node (ref "M1") (pin "1") (pintype "passive"))
      (node (ref "U5") (pin "10") (pinfunction "OUTB1_10") (pintype "passive"))
    )
    (net (code "53") (name "Net-(U5-OUTB2)") (class "Default")
      (node (ref "M1") (pin "2") (pintype "passive"))
      (node (ref "U5") (pin "8") (pinfunction "OUTB2_8") (pintype "passive"))
    )
    (net (code "54") (name "Net-(U5-REF)") (class "Default")
      (node (ref "R20") (pin "1") (pintype "passive"))
      (node (ref "R22") (pin "2") (pintype "passive"))
      (node (ref "U5") (pin "11") (pinfunction "REF_11") (pintype "input"))
    )
    (net (code "55") (name "Net-(U5-SENSEA)") (class "Default")
      (node (ref "R30") (pin "2") (pintype "passive"))
      (node (ref "U5") (pin "4") (pinfunction "SENSEA_4") (pintype "passive"))
    )
    (net (code "56") (name "Net-(U5-SENSEB)") (class "Default")
      (node (ref "R29") (pin "2") (pintype "passive"))
      (node (ref "U5") (pin "9") (pinfunction "SENSEB_9") (pintype "passive"))
    )
    (net (code "57") (name "Net-(U5-STBY{slash}RESET)") (class "Default")
      (node (ref "R13") (pin "1") (pintype "passive"))
      (node (ref "U5") (pin "14") (pinfunction "STBY/RESET_14") (pintype "input"))
    )
    (net (code "58") (name "Net-(U5-TOFF)") (class "Default")
      (node (ref "R27") (pin "2") (pintype "passive"))
      (node (ref "R28") (pin "2") (pintype "passive"))
      (node (ref "U5") (pin "12") (pinfunction "TOFF_12") (pintype "input"))
    )
    (net (code "59") (name "Net-(U6-Vout)") (class "Default")
      (node (ref "C19") (pin "1") (pinfunction "1_1") (pintype "passive"))
      (node (ref "R21") (pin "1") (pintype "passive"))
      (node (ref "U6") (pin "5") (pinfunction "Vout_5") (pintype "passive"))
    )
    (net (code "60") (name "Net-(X1-C1N)") (class "Default")
      (node (ref "C6") (pin "1") (pinfunction "1_1") (pintype "passive"))
      (node (ref "X1") (pin "4") (pinfunction "C1N_4") (pintype "passive"))
    )
    (net (code "61") (name "Net-(X1-C1P)") (class "Default")
      (node (ref "C6") (pin "2") (pinfunction "2_2") (pintype "passive"))
      (node (ref "X1") (pin "3") (pinfunction "C1P_3") (pintype "passive"))
    )
    (net (code "62") (name "Net-(X1-C2N)") (class "Default")
      (node (ref "C5") (pin "1") (pinfunction "1_1") (pintype "passive"))
      (node (ref "X1") (pin "2") (pinfunction "C2N_2") (pintype "passive"))
    )
    (net (code "63") (name "Net-(X1-C2P)") (class "Default")
      (node (ref "C5") (pin "2") (pinfunction "2_2") (pintype "passive"))
      (node (ref "X1") (pin "1") (pinfunction "C2P_1") (pintype "passive"))
    )
    (net (code "64") (name "Net-(X1-IREF)") (class "Default")
      (node (ref "R10") (pin "2") (pintype "passive"))
      (node (ref "X1") (pin "12") (pinfunction "IREF_12") (pintype "passive"))
    )
    (net (code "65") (name "Net-(X1-VCC)") (class "Default")
      (node (ref "C14") (pin "2") (pinfunction "2_2") (pintype "passive"))
      (node (ref "X1") (pin "14") (pinfunction "VCC_14") (pintype "passive"))
    )
    (net (code "66") (name "Net-(X1-VCOMH)") (class "Default")
      (node (ref "C13") (pin "2") (pinfunction "2_2") (pintype "passive"))
      (node (ref "X1") (pin "13") (pinfunction "VCOMH_13") (pintype "passive"))
    )
    (net (code "67") (name "VMOT") (class "Default")
      (node (ref "C15") (pin "1") (pintype "passive"))
      (node (ref "H1") (pin "4") (pintype "passive"))
      (node (ref "R11") (pin "1") (pintype "passive"))
      (node (ref "U5") (pin "6") (pinfunction "VS_6") (pintype "power_in"))
    )
    (net (code "68") (name "VUSB") (class "Default")
      (node (ref "C1") (pin "1") (pinfunction "1_1") (pintype "passive"))
      (node (ref "C11") (pin "1") (pinfunction "1_1") (pintype "passive"))
      (node (ref "C17") (pin "1") (pinfunction "1_1") (pintype "passive"))
      (node (ref "C18") (pin "1") (pinfunction "1_1") (pintype "passive"))
      (node (ref "F1") (pin "1") (pintype "passive"))
      (node (ref "R6") (pin "2") (pintype "passive"))
      (node (ref "S1") (pin "2") (pinfunction "2_2") (pintype "passive"))
      (node (ref "U1") (pin "7") (pinfunction "REGIN_7") (pintype "power_in"))
      (node (ref "U1") (pin "8") (pinfunction "VBUS_8") (pintype "power_in"))
      (node (ref "U4") (pin "4") (pinfunction "Vin_4") (pintype "passive"))
      (node (ref "U6") (pin "1") (pinfunction "Vin_1") (pintype "passive"))
      (node (ref "U7") (pin "5") (pinfunction "5_5") (pintype "passive"))
    )
    (net (code "69") (name "unconnected-(ANT1-Pad3)") (class "Default")
      (node (ref "ANT1") (pin "3") (pintype "passive+no_connect"))
    )
    (net (code "70") (name "unconnected-(ANT1-Pad4)") (class "Default")
      (node (ref "ANT1") (pin "4") (pintype "passive+no_connect"))
    )
    (net (code "71") (name "unconnected-(H1-Pad8)") (class "Default")
      (node (ref "H1") (pin "8") (pintype "passive"))
    )
    (net (code "72") (name "unconnected-(J1-DAT1-Pad8)") (class "Default")
      (node (ref "J1") (pin "8") (pinfunction "DAT1_8") (pintype "power_in+no_connect"))
    )
    (net (code "73") (name "unconnected-(J1-DAT2-Pad1)") (class "Default")
      (node (ref "J1") (pin "1") (pinfunction "DAT2_1") (pintype "power_in+no_connect"))
    )
    (net (code "74") (name "unconnected-(J2-ID-Pad4)") (class "Default")
      (node (ref "J2") (pin "4") (pinfunction "ID_4") (pintype "passive+no_connect"))
    )
    (net (code "75") (name "unconnected-(S1-Pad3)") (class "Default")
      (node (ref "S1") (pin "3") (pinfunction "3_3") (pintype "passive+no_connect"))
    )
    (net (code "76") (name "unconnected-(U1-CTS-Pad18)") (class "Default")
      (node (ref "U1") (pin "18") (pinfunction "CTS_18") (pintype "passive+no_connect"))
    )
    (net (code "77") (name "unconnected-(U1-DCD-Pad24)") (class "Default")
      (node (ref "U1") (pin "24") (pinfunction "DCD_24") (pintype "passive+no_connect"))
    )
    (net (code "78") (name "unconnected-(U1-DSR-Pad22)") (class "Default")
      (node (ref "U1") (pin "22") (pinfunction "DSR_22") (pintype "passive+no_connect"))
    )
    (net (code "79") (name "unconnected-(U1-GPIO.0-Pad14)") (class "Default")
      (node (ref "U1") (pin "14") (pinfunction "GPIO.0_14") (pintype "passive+no_connect"))
    )
    (net (code "80") (name "unconnected-(U1-GPIO.1-Pad13)") (class "Default")
      (node (ref "U1") (pin "13") (pinfunction "GPIO.1_13") (pintype "passive+no_connect"))
    )
    (net (code "81") (name "unconnected-(U1-GPIO.2-Pad12)") (class "Default")
      (node (ref "U1") (pin "12") (pinfunction "GPIO.2_12") (pintype "passive+no_connect"))
    )
    (net (code "82") (name "unconnected-(U1-GPIO.3-Pad11)") (class "Default")
      (node (ref "U1") (pin "11") (pinfunction "GPIO.3_11") (pintype "passive+no_connect"))
    )
    (net (code "83") (name "unconnected-(U1-NC-Pad10)") (class "Default")
      (node (ref "U1") (pin "10") (pinfunction "NC_10") (pintype "passive+no_connect"))
    )
    (net (code "84") (name "unconnected-(U1-RI-Pad1)") (class "Default")
      (node (ref "U1") (pin "1") (pinfunction "RI_1") (pintype "passive+no_connect"))
    )
    (net (code "85") (name "unconnected-(U1-SUSPEND-Pad17)") (class "Default")
      (node (ref "U1") (pin "17") (pinfunction "SUSPEND_17") (pintype "passive+no_connect"))
    )
    (net (code "86") (name "unconnected-(U1-VPP-Pad16)") (class "Default")
      (node (ref "U1") (pin "16") (pinfunction "VPP_16") (pintype "passive+no_connect"))
    )
    (net (code "87") (name "unconnected-(U1-~{SUSPEND}-Pad15)") (class "Default")
      (node (ref "U1") (pin "15") (pinfunction "~{SUSPEND}_15") (pintype "passive+no_connect"))
    )
    (net (code "88") (name "unconnected-(U2-CAP1_NC-Pad48)") (class "Default")
      (node (ref "U2") (pin "48") (pinfunction "CAP1_NC_48") (pintype "passive"))
    )
    (net (code "89") (name "unconnected-(U2-CAP2_NC-Pad47)") (class "Default")
      (node (ref "U2") (pin "47") (pinfunction "CAP2_NC_47") (pintype "passive"))
    )
    (net (code "90") (name "unconnected-(U2-GPIO5(I{slash}O)-Pad34)") (class "Default")
      (node (ref "U2") (pin "34") (pinfunction "GPIO5(I/O)_34") (pintype "passive"))
    )
    (net (code "91") (name "unconnected-(U2-IO16(No_Use)-Pad25)") (class "Default")
      (node (ref "U2") (pin "25") (pinfunction "IO16(No_Use)_25") (pintype "passive"))
    )
    (net (code "92") (name "unconnected-(U2-IO17(No_Use)-Pad27)") (class "Default")
      (node (ref "U2") (pin "27") (pinfunction "IO17(No_Use)_27") (pintype "passive"))
    )
    (net (code "93") (name "unconnected-(U2-SD_CLK-Pad31)") (class "Default")
      (node (ref "U2") (pin "31") (pinfunction "SD_CLK_31") (pintype "passive"))
    )
    (net (code "94") (name "unconnected-(U2-SD_CMD-Pad30)") (class "Default")
      (node (ref "U2") (pin "30") (pinfunction "SD_CMD_30") (pintype "passive"))
    )
    (net (code "95") (name "unconnected-(U2-SD_DATA_0-Pad32)") (class "Default")
      (node (ref "U2") (pin "32") (pinfunction "SD_DATA_0_32") (pintype "passive"))
    )
    (net (code "96") (name "unconnected-(U2-SD_DATA_1-Pad33)") (class "Default")
      (node (ref "U2") (pin "33") (pinfunction "SD_DATA_1_33") (pintype "passive"))
    )
    (net (code "97") (name "unconnected-(U2-SENSOR_CAPN-Pad7)") (class "Default")
      (node (ref "U2") (pin "7") (pinfunction "SENSOR_CAPN_7") (pintype "passive"))
    )
    (net (code "98") (name "unconnected-(U2-SENSOR_CAPP-Pad6)") (class "Default")
      (node (ref "U2") (pin "6") (pinfunction "SENSOR_CAPP_6") (pintype "passive"))
    )
    (net (code "99") (name "unconnected-(U2-SENSOR_VN-Pad8)") (class "Default")
      (node (ref "U2") (pin "8") (pinfunction "SENSOR_VN_8") (pintype "passive"))
    )
    (net (code "100") (name "unconnected-(U2-SENSOR_VP-Pad5)") (class "Default")
      (node (ref "U2") (pin "5") (pinfunction "SENSOR_VP_5") (pintype "passive"))
    )
    (net (code "101") (name "unconnected-(U2-VDD_SDIO_NC-Pad26)") (class "Default")
      (node (ref "U2") (pin "26") (pinfunction "VDD_SDIO_NC_26") (pintype "power_in"))
    )
    (net (code "102") (name "unconnected-(U2-XTAL_N_NC-Pad44)") (class "Default")
      (node (ref "U2") (pin "44") (pinfunction "XTAL_N_NC_44") (pintype "passive"))
    )
    (net (code "103") (name "unconnected-(U2-XTAL_P_NC-Pad45)") (class "Default")
      (node (ref "U2") (pin "45") (pinfunction "XTAL_P_NC_45") (pintype "passive"))
    )
    (net (code "104") (name "unconnected-(U3-NC-Pad4)") (class "Default")
      (node (ref "U3") (pin "4") (pinfunction "NC_4") (pintype "passive+no_connect"))
    )
    (net (code "105") (name "unconnected-(U6-NC-Pad4)") (class "Default")
      (node (ref "U6") (pin "4") (pinfunction "NC_4") (pintype "passive+no_connect"))
    )
    (net (code "106") (name "unconnected-(U7-Pad3)") (class "Default")
      (node (ref "U7") (pin "3") (pinfunction "3_3") (pintype "passive"))
    )
    (net (code "107") (name "unconnected-(U7-Pad4)") (class "Default")
      (node (ref "U7") (pin "4") (pinfunction "4_4") (pintype "passive"))
    )
  )
)
